# Encoder.net
KiCad netlist of a schematic drawn in Altium Designer
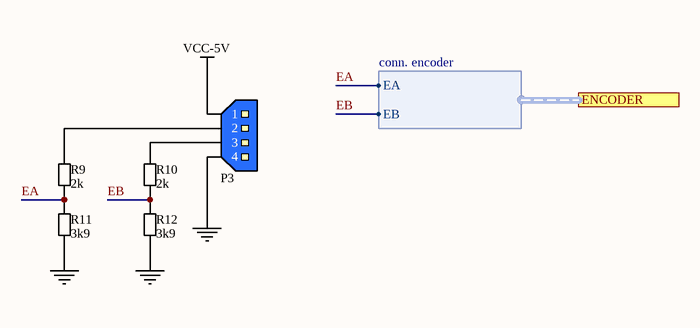
[diagram p0: Encoder.SchDoc]

(export (version "E")
  (design (tool "Eeschema 10.0.6"))
  (components
    (comp (ref "P3")
      (value "TE CONNECTIVITY_4PIN_MALE")
      (footprint "TE CONNECTIVITY_4PIN_MALE")
      (description "BLUE_4PIN_CONECTOR")
      (fields (field (name "MANUFACTURER") "TE CONNECTIVITY / AMP"))
      (libsource (lib "Electro_Mechanical") (part "TE CONNECTIVITY_4PIN_MALE"))
    )
    (comp (ref "R9")
      (value "2k")
      (footprint "RESC2013X38N-0805-NOOVERLAY")
      (description "RES SMD 2 kOhm 1/8W 0805")
      (fields (field (name "POWER") "0.125W, 1/8W"))
      (libsource (lib "Resistors") (part "00002001"))
    )
    (comp (ref "R10")
      (value "2k")
      (footprint "RESC2013X38N-0805-NOOVERLAY")
      (description "RES SMD 2 kOhm 1/8W 0805")
      (fields (field (name "POWER") "0.125W, 1/8W"))
      (libsource (lib "Resistors") (part "00002001"))
    )
    (comp (ref "R11")
      (value "3k9")
      (footprint "RESC2013X38N-0805-NOOVERLAY")
      (description "RES SMD 3.9 kOhm 1/8W 0805")
      (fields (field (name "POWER") "0.125W, 1/8W"))
      (libsource (lib "Resistors") (part "00003901"))
    )
    (comp (ref "R12")
      (value "3k9")
      (footprint "RESC2013X38N-0805-NOOVERLAY")
      (description "RES SMD 3.9 kOhm 1/8W 0805")
      (fields (field (name "POWER") "0.125W, 1/8W"))
      (libsource (lib "Resistors") (part "00003901"))
    )
  )
  (nets
    (net (code "3") (name "/EA") (class "Default")
      (node (ref "R11") (pin "2") (pinfunction "2_2") (pintype "passive"))
      (node (ref "R9") (pin "1") (pinfunction "1_1") (pintype "passive"))
    )
    (net (code "4") (name "/EB") (class "Default")
      (node (ref "R10") (pin "1") (pinfunction "1_1") (pintype "passive"))
      (node (ref "R12") (pin "2") (pinfunction "2_2") (pintype "passive"))
    )
    (net (code "6") (name "GND") (class "Default")
      (node (ref "P3") (pin "4") (pinfunction "4_4") (pintype "passive"))
      (node (ref "R11") (pin "1") (pinfunction "1_1") (pintype "passive"))
      (node (ref "R12") (pin "1") (pinfunction "1_1") (pintype "passive"))
    )
    (net (code "7") (name "Net-(P3-Pad2)") (class "Default")
      (node (ref "P3") (pin "2") (pinfunction "2_2") (pintype "passive"))
      (node (ref "R9") (pin "2") (pinfunction "2_2") (pintype "passive"))
    )
    (net (code "8") (name "Net-(P3-Pad3)") (class "Default")
      (node (ref "P3") (pin "3") (pinfunction "3_3") (pintype "passive"))
      (node (ref "R10") (pin "2") (pinfunction "2_2") (pintype "passive"))
    )
    (net (code "9") (name "VCC-5V") (class "Default")
      (node (ref "P3") (pin "1") (pinfunction "1_1") (pintype "passive"))
    )
  )
)
